# SFP.net
KiCad netlist of a schematic drawn in Altium Designer
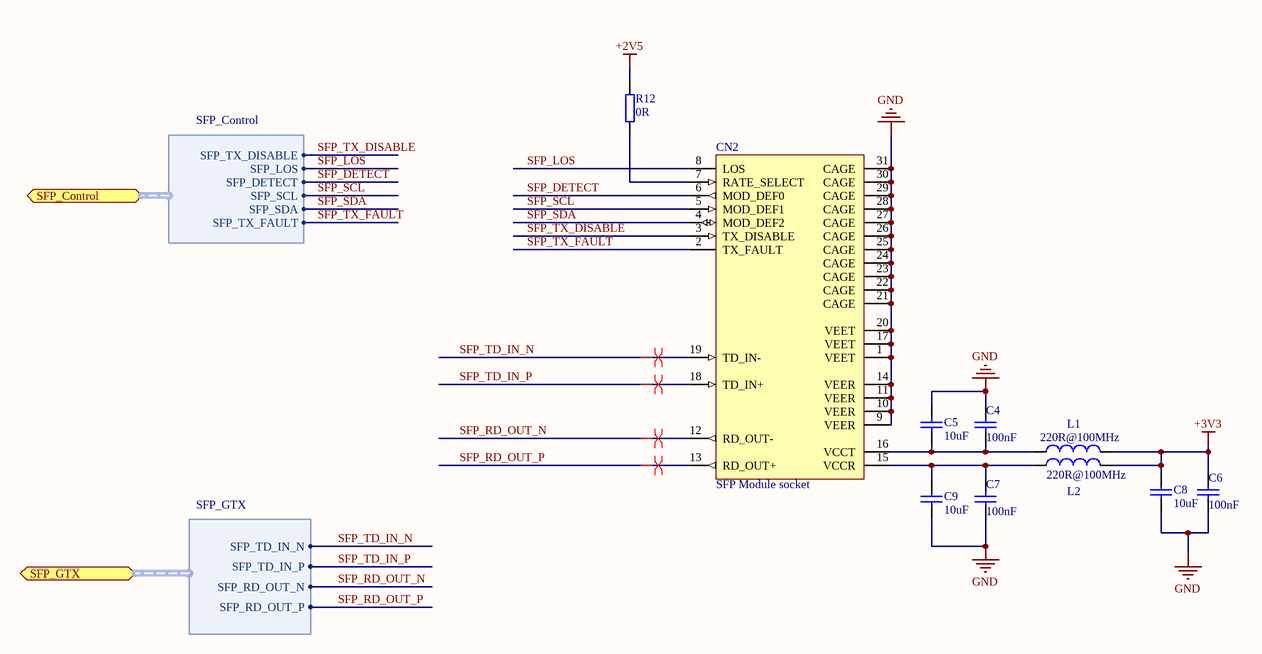
[diagram p0: SFP.SchDoc]

(export (version "E")
  (design (tool "Eeschema 10.0.6"))
  (components
    (comp (ref "C4")
      (value "100nF")
      (footprint "CC1608-0603")
      (description "Capacitor")
      (fields
        (field (name "TOLERANCE") "±10%")
        (field (name "VOLTAGE") "16V")
        (field (name "PUBLISHER") "Altium Limited")
      )
      (libsource (lib "wr_switch") (part "Cap"))
    )
    (comp (ref "C5")
      (value "10uF")
      (footprint "CC1608-0603")
      (description "Capacitor")
      (fields
        (field (name "TOLERANCE") "±20%")
        (field (name "VOLTAGE") "6.3V")
        (field (name "PUBLISHER") "Altium Limited")
      )
      (libsource (lib "wr_switch") (part "Cap"))
    )
    (comp (ref "C6")
      (value "100nF")
      (footprint "CC1608-0603")
      (description "Capacitor")
      (fields
        (field (name "TOLERANCE") "±10%")
        (field (name "VOLTAGE") "16V")
        (field (name "PUBLISHER") "Altium Limited")
      )
      (libsource (lib "wr_switch") (part "Cap"))
    )
    (comp (ref "C7")
      (value "100nF")
      (footprint "CC1608-0603")
      (description "Capacitor")
      (fields
        (field (name "TOLERANCE") "±10%")
        (field (name "VOLTAGE") "16V")
        (field (name "PUBLISHER") "Altium Limited")
      )
      (libsource (lib "wr_switch") (part "Cap"))
    )
    (comp (ref "C8")
      (value "10uF")
      (footprint "CC1608-0603")
      (description "Capacitor")
      (fields
        (field (name "TOLERANCE") "±20%")
        (field (name "VOLTAGE") "6.3V")
        (field (name "PUBLISHER") "Altium Limited")
      )
      (libsource (lib "wr_switch") (part "Cap"))
    )
    (comp (ref "C9")
      (value "10uF")
      (footprint "CC1608-0603")
      (description "Capacitor")
      (fields
        (field (name "TOLERANCE") "±20%")
        (field (name "VOLTAGE") "6.3V")
        (field (name "PUBLISHER") "Altium Limited")
      )
      (libsource (lib "wr_switch") (part "Cap"))
    )
    (comp (ref "CN2")
      (value "SFP Module socket")
      (footprint "7S_WR:SFP_SINGLE_PORT")
      (description "Socket for SFP module")
      (libsource (lib "wr_switch") (part "SFP_SOCKET_SINGLE"))
    )
    (comp (ref "L1")
      (value "220R@100MHz Ferrite Bead")
      (footprint "0603")
      (description "ferrite bead")
      (fields (field (name "IMPEDANCE") "220R@100MHz"))
      (libsource (lib "wr_switch") (part "L_FERRITE_BEAD"))
    )
    (comp (ref "L2")
      (value "220R@100MHz Ferrite Bead")
      (footprint "0603")
      (description "ferrite bead")
      (fields (field (name "IMPEDANCE") "220R@100MHz"))
      (libsource (lib "wr_switch") (part "L_FERRITE_BEAD"))
    )
    (comp (ref "R12")
      (value "0R")
      (footprint "0603")
      (description "SMD Resistor")
      (libsource (lib "wr_switch") (part "RES_SMD"))
    )
  )
  (nets
    (net (code "3") (name "+2V5") (class "Default")
      (node (ref "R12") (pin "1") (pinfunction "1_1") (pintype "passive"))
    )
    (net (code "4") (name "+3V3") (class "Default")
      (node (ref "C6") (pin "1") (pinfunction "1_1") (pintype "passive"))
      (node (ref "C8") (pin "1") (pinfunction "1_1") (pintype "passive"))
      (node (ref "L1") (pin "2") (pinfunction "2_2") (pintype "passive"))
      (node (ref "L2") (pin "2") (pinfunction "2_2") (pintype "passive"))
    )
    (net (code "5") (name "/SFP_DETECT") (class "Default")
      (node (ref "CN2") (pin "6") (pinfunction "MOD_DEF0_6") (pintype "output"))
    )
    (net (code "6") (name "/SFP_LOS") (class "Default")
      (node (ref "CN2") (pin "8") (pinfunction "LOS_8") (pintype "open_collector"))
    )
    (net (code "7") (name "/SFP_RD_OUT_N") (class "Default")
      (node (ref "CN2") (pin "12") (pinfunction "RD_OUT-_12") (pintype "output"))
    )
    (net (code "8") (name "/SFP_RD_OUT_P") (class "Default")
      (node (ref "CN2") (pin "13") (pinfunction "RD_OUT+_13") (pintype "output"))
    )
    (net (code "9") (name "/SFP_SCL") (class "Default")
      (node (ref "CN2") (pin "5") (pinfunction "MOD_DEF1_5") (pintype "input"))
    )
    (net (code "10") (name "/SFP_SDA") (class "Default")
      (node (ref "CN2") (pin "4") (pinfunction "MOD_DEF2_4") (pintype "bidirectional"))
    )
    (net (code "11") (name "/SFP_TD_IN_N") (class "Default")
      (node (ref "CN2") (pin "19") (pinfunction "TD_IN-_19") (pintype "input"))
    )
    (net (code "12") (name "/SFP_TD_IN_P") (class "Default")
      (node (ref "CN2") (pin "18") (pinfunction "TD_IN+_18") (pintype "input"))
    )
    (net (code "13") (name "/SFP_TX_DISABLE") (class "Default")
      (node (ref "CN2") (pin "3") (pinfunction "TX_DISABLE_3") (pintype "input"))
    )
    (net (code "14") (name "/SFP_TX_FAULT") (class "Default")
      (node (ref "CN2") (pin "2") (pinfunction "TX_FAULT_2") (pintype "open_collector"))
    )
    (net (code "17") (name "GND") (class "Default")
      (node (ref "C4") (pin "1") (pinfunction "1_1") (pintype "passive"))
      (node (ref "C5") (pin "1") (pinfunction "1_1") (pintype "passive"))
      (node (ref "C6") (pin "2") (pinfunction "2_2") (pintype "passive"))
      (node (ref "C7") (pin "2") (pinfunction "2_2") (pintype "passive"))
      (node (ref "C8") (pin "2") (pinfunction "2_2") (pintype "passive"))
      (node (ref "C9") (pin "2") (pinfunction "2_2") (pintype "passive"))
      (node (ref "CN2") (pin "1") (pinfunction "VEET_1") (pintype "power_in"))
      (node (ref "CN2") (pin "10") (pinfunction "VEER_10") (pintype "power_in"))
      (node (ref "CN2") (pin "11") (pinfunction "VEER_11") (pintype "power_in"))
      (node (ref "CN2") (pin "14") (pinfunction "VEER_14") (pintype "power_in"))
      (node (ref "CN2") (pin "17") (pinfunction "VEET_17") (pintype "power_in"))
      (node (ref "CN2") (pin "20") (pinfunction "VEET_20") (pintype "power_in"))
      (node (ref "CN2") (pin "21") (pinfunction "CAGE_21") (pintype "power_in"))
      (node (ref "CN2") (pin "22") (pinfunction "CAGE_22") (pintype "power_in"))
      (node (ref "CN2") (pin "23") (pinfunction "CAGE_23") (pintype "power_in"))
      (node (ref "CN2") (pin "24") (pinfunction "CAGE_24") (pintype "power_in"))
      (node (ref "CN2") (pin "25") (pinfunction "CAGE_25") (pintype "power_in"))
      (node (ref "CN2") (pin "26") (pinfunction "CAGE_26") (pintype "power_in"))
      (node (ref "CN2") (pin "27") (pinfunction "CAGE_27") (pintype "power_in"))
      (node (ref "CN2") (pin "28") (pinfunction "CAGE_28") (pintype "power_in"))
      (node (ref "CN2") (pin "29") (pinfunction "CAGE_29") (pintype "power_in"))
      (node (ref "CN2") (pin "30") (pinfunction "CAGE_30") (pintype "power_in"))
      (node (ref "CN2") (pin "31") (pinfunction "CAGE_31") (pintype "power_in"))
      (node (ref "CN2") (pin "9") (pinfunction "VEER_9") (pintype "power_in"))
    )
    (net (code "18") (name "Net-(CN2-RATE_SELECT)") (class "Default")
      (node (ref "CN2") (pin "7") (pinfunction "RATE_SELECT_7") (pintype "input"))
      (node (ref "R12") (pin "2") (pinfunction "2_2") (pintype "passive"))
    )
    (net (code "19") (name "Net-(CN2-VCCR)") (class "Default")
      (node (ref "C7") (pin "1") (pinfunction "1_1") (pintype "passive"))
      (node (ref "C9") (pin "1") (pinfunction "1_1") (pintype "passive"))
      (node (ref "CN2") (pin "15") (pinfunction "VCCR_15") (pintype "power_in"))
      (node (ref "L2") (pin "1") (pinfunction "1_1") (pintype "passive"))
    )
    (net (code "20") (name "Net-(CN2-VCCT)") (class "Default")
      (node (ref "C4") (pin "2") (pinfunction "2_2") (pintype "passive"))
      (node (ref "C5") (pin "2") (pinfunction "2_2") (pintype "passive"))
      (node (ref "CN2") (pin "16") (pinfunction "VCCT_16") (pintype "power_in"))
      (node (ref "L1") (pin "1") (pinfunction "1_1") (pintype "passive"))
    )
  )
)
